# Regulator.net
KiCad netlist of a schematic drawn in Altium Designer
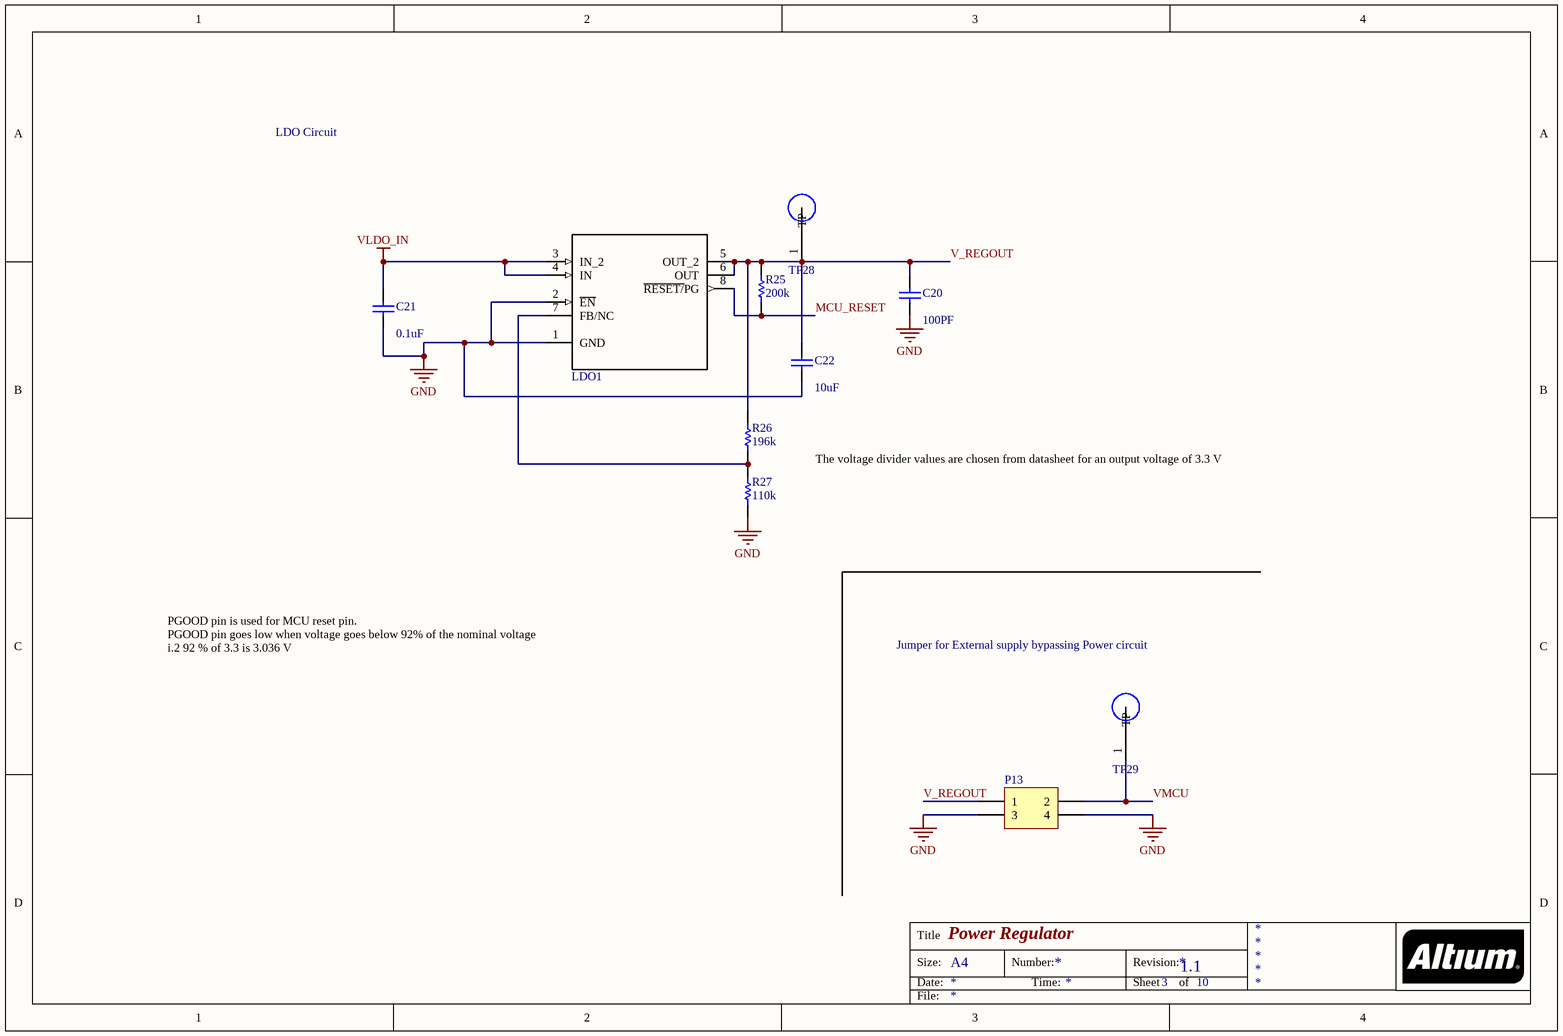
[diagram p0: Regulator.SchDoc]

(export (version "E")
  (design (tool "Eeschema 10.0.6"))
  (components
    (comp (ref "C20")
      (value "100PF")
      (footprint "C0805")
      (description "CAP CER 100PF 50V C0G/NP0 0805")
      (fields (field (name "DIGI-KEY PART NUMBER") "399-1122-1-ND") (field (name "MANUFACTURER") "KEMET"))
      (libsource (lib "Miscellaneous Devices") (part "Cap"))
    )
    (comp (ref "C21")
      (value "0.1uF")
      (footprint "1608[0603]")
      (description "10000pF ±10% 50V Ceramic Capacitor X7R 0603 (1608 Metric)")
      (fields
        (field (name "DIGI-KEY PART NUMBER") "1276-1009-1-ND")
        (field (name "MANUFACTURER") "Samsung Electro-Mechanics")
      )
      (libsource (lib "Miscellaneous Devices") (part "Cap"))
    )
    (comp (ref "C22")
      (value "10uF")
      (footprint "1608[0603]")
      (description "10000pF ±10% 50V Ceramic Capacitor X7R 0603 (1608 Metric)")
      (fields
        (field (name "DIGI-KEY PART NUMBER") "1276-1009-1-ND")
        (field (name "MANUFACTURER") "Samsung Electro-Mechanics")
      )
      (libsource (lib "Miscellaneous Devices") (part "Cap"))
    )
    (comp (ref "LDO1")
      (value "LDO")
      (footprint "LDO")
      (description "IC REG LINEAR 3.3V 750MA 8SOIC")
      (fields
        (field (name "MANUFACTURER") "Texas Instruments")
        (field (name "MANUFACTURER PART NUMBER") "TPS77833D")
      )
      (libsource (lib "LDO") (part "LDO"))
    )
    (comp (ref "P13")
      (value "Header 2X2H")
      (footprint "HDR2X2H")
      (description "CONN HEADER VERT 8POS 2.54MM")
      (fields
        (field (name "DIGI-KEY PART NUMBER") "A121467-ND")
        (field (name "MANUFACTURER") "TE Connectivity AMP Connectors")
      )
      (libsource (lib "Miscellaneous Connectors") (part "Header 2X2H"))
    )
    (comp (ref "R25")
      (value "200k")
      (footprint "1608[0603]")
      (fields
        (field (name "DIGI-KEY PART NUMBER") "RNCP0603FTD10K0CT-ND")
        (field (name "MANUFACTURER") "Stackpole Electronics Inc")
        (field (name "MANUFACTURER PART NUMBER") "RNCP0603FTD10K0")
      )
      (libsource (lib "Miscellaneous Devices") (part "Res1"))
    )
    (comp (ref "R26")
      (value "196k")
      (footprint "1608[0603]")
      (fields
        (field (name "DIGI-KEY PART NUMBER") "RNCP0603FTD10K0CT-ND")
        (field (name "MANUFACTURER") "Stackpole Electronics Inc")
        (field (name "MANUFACTURER PART NUMBER") "RNCP0603FTD10K0")
      )
      (libsource (lib "Miscellaneous Devices") (part "Res1"))
    )
    (comp (ref "R27")
      (value "110k")
      (footprint "1608[0603]")
      (fields
        (field (name "DIGI-KEY PART NUMBER") "RNCP0603FTD10K0CT-ND")
        (field (name "MANUFACTURER") "Stackpole Electronics Inc")
        (field (name "MANUFACTURER PART NUMBER") "RNCP0603FTD10K0")
      )
      (libsource (lib "Miscellaneous Devices") (part "Res1"))
    )
    (comp (ref "TP28")
      (value "TP")
      (footprint "TP")
      (description "PC TEST POINT MINIATURE")
      (fields
        (field (name "MANUFACTURER") "Keystone Electronics")
        (field (name "DIGI-KEY PART NUMBER") "36-5019CT-ND")
      )
      (libsource (lib "TP") (part "TP"))
    )
    (comp (ref "TP29")
      (value "TP")
      (footprint "TP")
      (description "PC TEST POINT MINIATURE")
      (fields
        (field (name "MANUFACTURER") "Keystone Electronics")
        (field (name "DIGI-KEY PART NUMBER") "36-5019CT-ND")
      )
      (libsource (lib "TP") (part "TP"))
    )
  )
  (nets
    (net (code "1") (name "/MCU_RESET") (class "Default")
      (node (ref "LDO1") (pin "8") (pinfunction "~{RESET/}PG_8") (pintype "output"))
      (node (ref "R25") (pin "2") (pinfunction "2_2") (pintype "passive"))
    )
    (net (code "2") (name "/VMCU") (class "Default")
      (node (ref "P13") (pin "2") (pinfunction "2_2") (pintype "passive"))
      (node (ref "TP29") (pin "1") (pinfunction "TP_1") (pintype "passive"))
    )
    (net (code "3") (name "/V_REGOUT") (class "Default")
      (node (ref "C20") (pin "2") (pinfunction "2_2") (pintype "passive"))
      (node (ref "C22") (pin "2") (pinfunction "2_2") (pintype "passive"))
      (node (ref "LDO1") (pin "5") (pinfunction "OUT_2_5") (pintype "power_in"))
      (node (ref "LDO1") (pin "6") (pinfunction "OUT_6") (pintype "power_in"))
      (node (ref "P13") (pin "1") (pinfunction "1_1") (pintype "passive"))
      (node (ref "R25") (pin "1") (pinfunction "1_1") (pintype "passive"))
      (node (ref "R26") (pin "1") (pinfunction "1_1") (pintype "passive"))
      (node (ref "TP28") (pin "1") (pinfunction "TP_1") (pintype "passive"))
    )
    (net (code "4") (name "GND") (class "Default")
      (node (ref "C20") (pin "1") (pinfunction "1_1") (pintype "passive"))
      (node (ref "C21") (pin "1") (pinfunction "1_1") (pintype "passive"))
      (node (ref "C22") (pin "1") (pinfunction "1_1") (pintype "passive"))
      (node (ref "LDO1") (pin "1") (pinfunction "GND_1") (pintype "passive"))
      (node (ref "LDO1") (pin "2") (pinfunction "~{EN}_2") (pintype "input"))
      (node (ref "P13") (pin "3") (pinfunction "3_3") (pintype "passive"))
      (node (ref "P13") (pin "4") (pinfunction "4_4") (pintype "passive"))
      (node (ref "R27") (pin "2") (pinfunction "2_2") (pintype "passive"))
    )
    (net (code "5") (name "Net-(LDO1-FB{slash}NC)") (class "Default")
      (node (ref "LDO1") (pin "7") (pinfunction "FB/NC_7") (pintype "passive"))
      (node (ref "R26") (pin "2") (pinfunction "2_2") (pintype "passive"))
      (node (ref "R27") (pin "1") (pinfunction "1_1") (pintype "passive"))
    )
    (net (code "6") (name "VLDO_IN") (class "Default")
      (node (ref "C21") (pin "2") (pinfunction "2_2") (pintype "passive"))
      (node (ref "LDO1") (pin "3") (pinfunction "IN_2_3") (pintype "input"))
      (node (ref "LDO1") (pin "4") (pinfunction "IN_4") (pintype "input"))
    )
  )
)
